# Sensor_Carousel.net
KiCad netlist of a schematic drawn in EAGLE
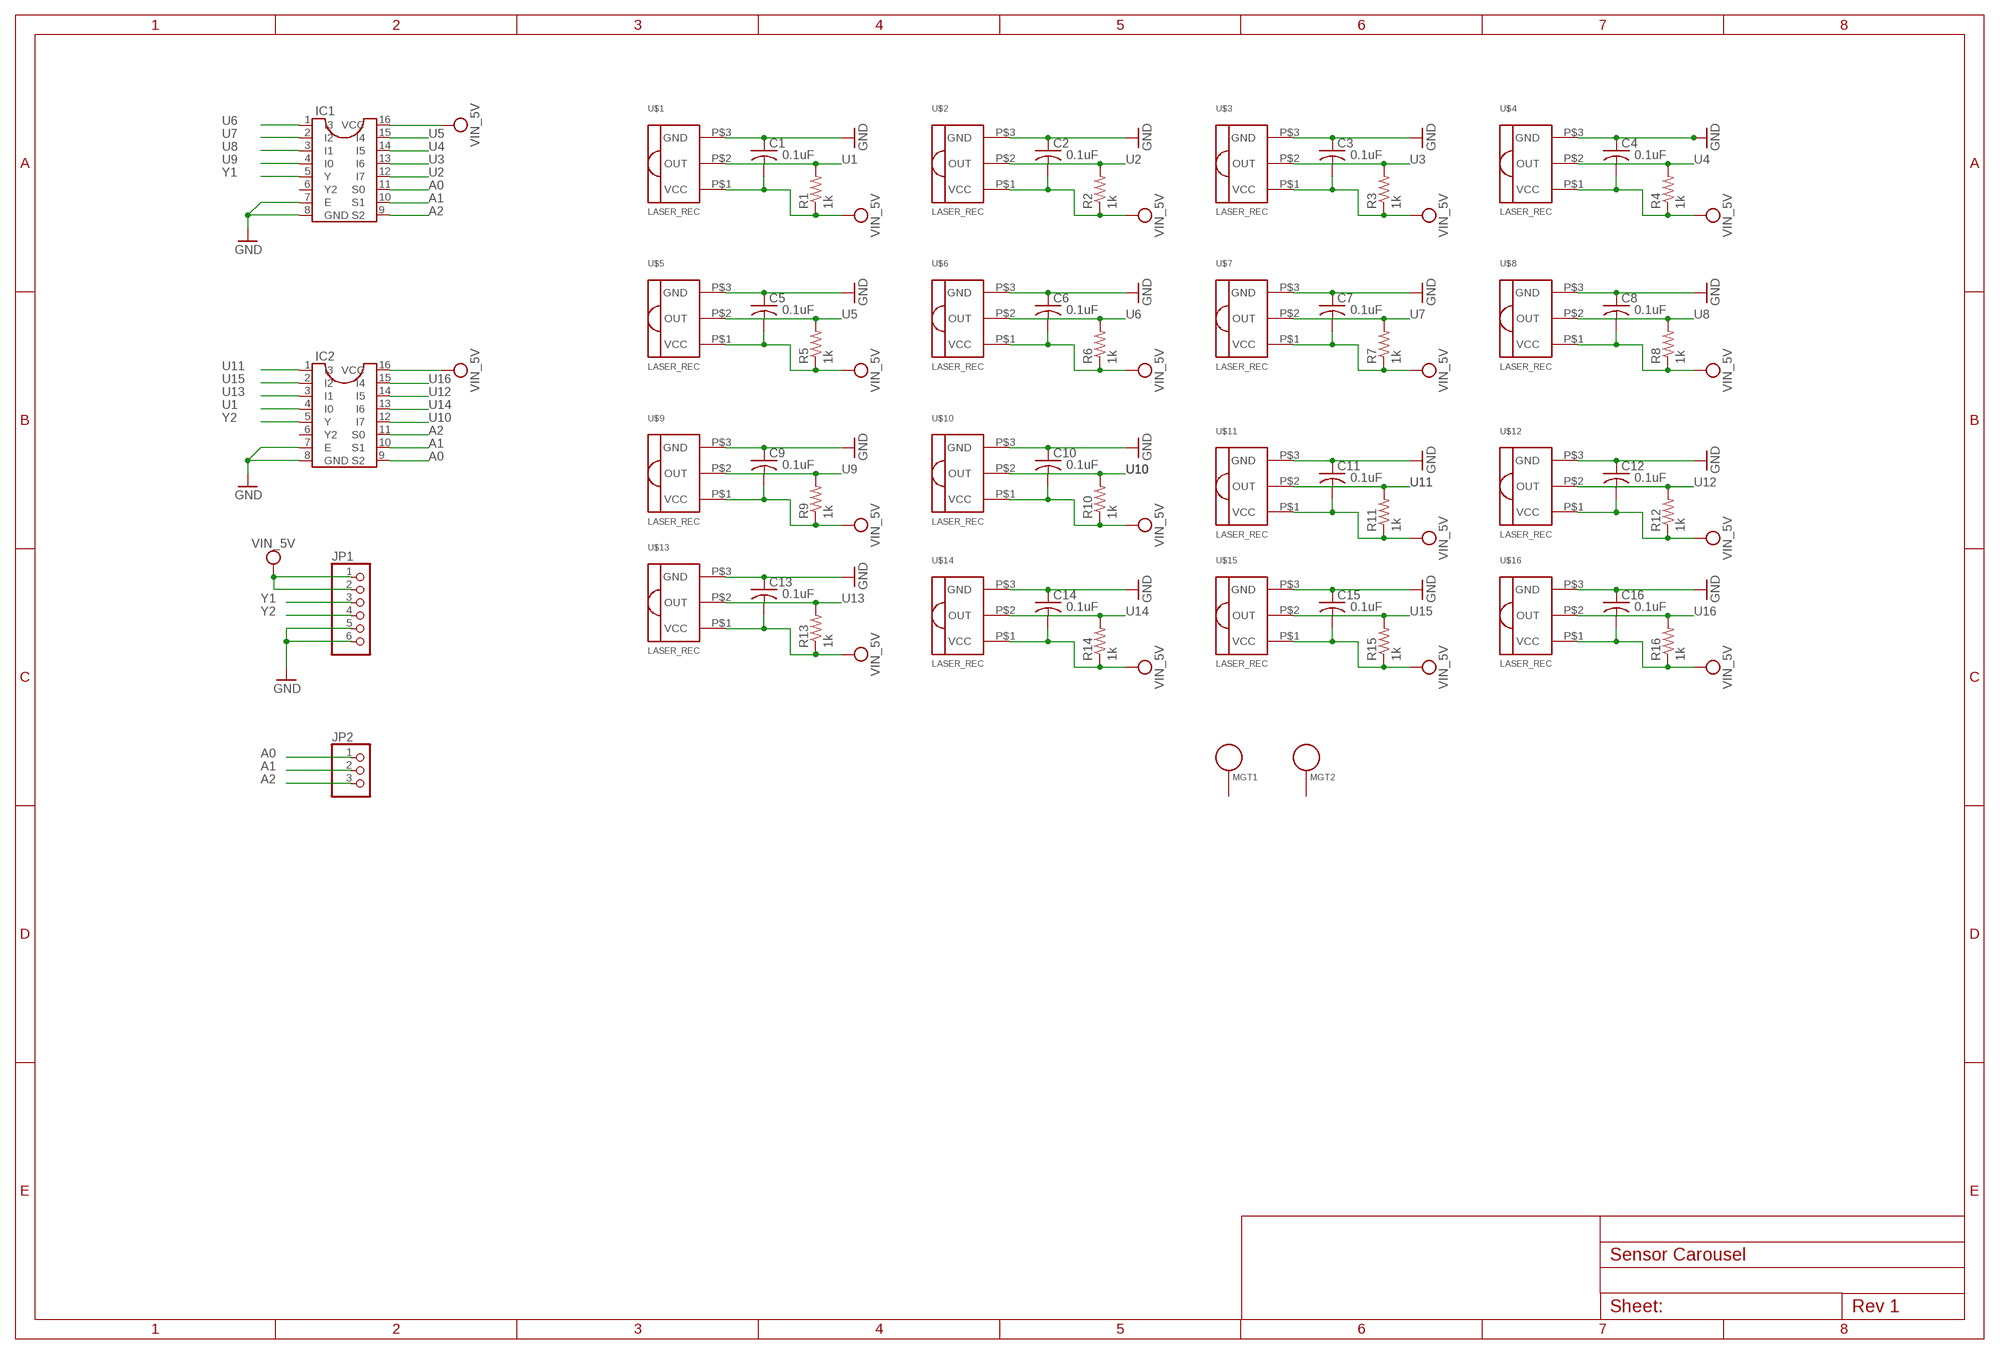
[diagram p0: schematic, sheet 1]

(export (version "E")
  (design (tool "Eeschema 10.0.6"))
  (components
    (comp (ref "C1")
      (value "0.1uF")
      (footprint "eagle-import:C025-024X044")
      (libsource (lib "eagle-import") (part "C-US025-024X044"))
    )
    (comp (ref "C2")
      (value "0.1uF")
      (footprint "eagle-import:C025-024X044")
      (libsource (lib "eagle-import") (part "C-US025-024X044"))
    )
    (comp (ref "C3")
      (value "0.1uF")
      (footprint "eagle-import:C025-024X044")
      (libsource (lib "eagle-import") (part "C-US025-024X044"))
    )
    (comp (ref "C4")
      (value "0.1uF")
      (footprint "eagle-import:C025-024X044")
      (libsource (lib "eagle-import") (part "C-US025-024X044"))
    )
    (comp (ref "C5")
      (value "0.1uF")
      (footprint "eagle-import:C025-024X044")
      (libsource (lib "eagle-import") (part "C-US025-024X044"))
    )
    (comp (ref "C6")
      (value "0.1uF")
      (footprint "eagle-import:C025-024X044")
      (libsource (lib "eagle-import") (part "C-US025-024X044"))
    )
    (comp (ref "C7")
      (value "0.1uF")
      (footprint "eagle-import:C025-024X044")
      (libsource (lib "eagle-import") (part "C-US025-024X044"))
    )
    (comp (ref "C8")
      (value "0.1uF")
      (footprint "eagle-import:C025-024X044")
      (libsource (lib "eagle-import") (part "C-US025-024X044"))
    )
    (comp (ref "C9")
      (value "0.1uF")
      (footprint "eagle-import:C025-024X044")
      (libsource (lib "eagle-import") (part "C-US025-024X044"))
    )
    (comp (ref "C10")
      (value "0.1uF")
      (footprint "eagle-import:C025-024X044")
      (libsource (lib "eagle-import") (part "C-US025-024X044"))
    )
    (comp (ref "C11")
      (value "0.1uF")
      (footprint "eagle-import:C025-024X044")
      (libsource (lib "eagle-import") (part "C-US025-024X044"))
    )
    (comp (ref "C12")
      (value "0.1uF")
      (footprint "eagle-import:C025-024X044")
      (libsource (lib "eagle-import") (part "C-US025-024X044"))
    )
    (comp (ref "C13")
      (value "0.1uF")
      (footprint "eagle-import:C025-024X044")
      (libsource (lib "eagle-import") (part "C-US025-024X044"))
    )
    (comp (ref "C14")
      (value "0.1uF")
      (footprint "eagle-import:C025-024X044")
      (libsource (lib "eagle-import") (part "C-US025-024X044"))
    )
    (comp (ref "C15")
      (value "0.1uF")
      (footprint "eagle-import:C025-024X044")
      (libsource (lib "eagle-import") (part "C-US025-024X044"))
    )
    (comp (ref "C16")
      (value "0.1uF")
      (footprint "eagle-import:C025-024X044")
      (libsource (lib "eagle-import") (part "C-US025-024X044"))
    )
    (comp (ref "IC1")
      (value "CD74HCT151S")
      (footprint "eagle-import:CD74HCT151")
      (libsource (lib "eagle-import") (part "CD74HCT151S"))
    )
    (comp (ref "IC2")
      (value "CD74HCT151S")
      (footprint "eagle-import:CD74HCT151")
      (libsource (lib "eagle-import") (part "CD74HCT151S"))
    )
    (comp (ref "JP1")
      (value "PINHD-1X6")
      (footprint "eagle-import:1X06")
      (libsource (lib "eagle-import") (part "PINHD-1X6"))
    )
    (comp (ref "JP2")
      (value "PINHD-1X3")
      (footprint "eagle-import:1X03")
      (libsource (lib "eagle-import") (part "PINHD-1X3"))
    )
    (comp (ref "MGT1")
      (value "MOUNTING_HOLE")
      (footprint "eagle-import:MOUNTING_HOLE")
      (libsource (lib "eagle-import") (part "MOUNTING_HOLE"))
    )
    (comp (ref "MGT2")
      (value "MOUNTING_HOLE")
      (footprint "eagle-import:MOUNTING_HOLE")
      (libsource (lib "eagle-import") (part "MOUNTING_HOLE"))
    )
    (comp (ref "R1")
      (value "1k")
      (footprint "eagle-import:0204V")
      (libsource (lib "eagle-import") (part "R-US_0204/2V"))
    )
    (comp (ref "R2")
      (value "1k")
      (footprint "eagle-import:0204V")
      (libsource (lib "eagle-import") (part "R-US_0204/2V"))
    )
    (comp (ref "R3")
      (value "1k")
      (footprint "eagle-import:0204V")
      (libsource (lib "eagle-import") (part "R-US_0204/2V"))
    )
    (comp (ref "R4")
      (value "1k")
      (footprint "eagle-import:0204V")
      (libsource (lib "eagle-import") (part "R-US_0204/2V"))
    )
    (comp (ref "R5")
      (value "1k")
      (footprint "eagle-import:0204V")
      (libsource (lib "eagle-import") (part "R-US_0204/2V"))
    )
    (comp (ref "R6")
      (value "1k")
      (footprint "eagle-import:0204V")
      (libsource (lib "eagle-import") (part "R-US_0204/2V"))
    )
    (comp (ref "R7")
      (value "1k")
      (footprint "eagle-import:0204V")
      (libsource (lib "eagle-import") (part "R-US_0204/2V"))
    )
    (comp (ref "R8")
      (value "1k")
      (footprint "eagle-import:0204V")
      (libsource (lib "eagle-import") (part "R-US_0204/2V"))
    )
    (comp (ref "R9")
      (value "1k")
      (footprint "eagle-import:0204V")
      (libsource (lib "eagle-import") (part "R-US_0204/2V"))
    )
    (comp (ref "R10")
      (value "1k")
      (footprint "eagle-import:0204V")
      (libsource (lib "eagle-import") (part "R-US_0204/2V"))
    )
    (comp (ref "R11")
      (value "1k")
      (footprint "eagle-import:0204V")
      (libsource (lib "eagle-import") (part "R-US_0204/2V"))
    )
    (comp (ref "R12")
      (value "1k")
      (footprint "eagle-import:0204V")
      (libsource (lib "eagle-import") (part "R-US_0204/2V"))
    )
    (comp (ref "R13")
      (value "1k")
      (footprint "eagle-import:0204V")
      (libsource (lib "eagle-import") (part "R-US_0204/2V"))
    )
    (comp (ref "R14")
      (value "1k")
      (footprint "eagle-import:0204V")
      (libsource (lib "eagle-import") (part "R-US_0204/2V"))
    )
    (comp (ref "R15")
      (value "1k")
      (footprint "eagle-import:0204V")
      (libsource (lib "eagle-import") (part "R-US_0204/2V"))
    )
    (comp (ref "R16")
      (value "1k")
      (footprint "eagle-import:0204V")
      (libsource (lib "eagle-import") (part "R-US_0204/2V"))
    )
    (comp (ref "U$1")
      (value "LASER_REC")
      (footprint "eagle-import:LSR_RC")
      (libsource (lib "eagle-import") (part "LASER_REC"))
    )
    (comp (ref "U$2")
      (value "LASER_REC")
      (footprint "eagle-import:LSR_RC")
      (libsource (lib "eagle-import") (part "LASER_REC"))
    )
    (comp (ref "U$3")
      (value "LASER_REC")
      (footprint "eagle-import:LSR_RC")
      (libsource (lib "eagle-import") (part "LASER_REC"))
    )
    (comp (ref "U$4")
      (value "LASER_REC")
      (footprint "eagle-import:LSR_RC")
      (libsource (lib "eagle-import") (part "LASER_REC"))
    )
    (comp (ref "U$5")
      (value "LASER_REC")
      (footprint "eagle-import:LSR_RC")
      (libsource (lib "eagle-import") (part "LASER_REC"))
    )
    (comp (ref "U$6")
      (value "LASER_REC")
      (footprint "eagle-import:LSR_RC")
      (libsource (lib "eagle-import") (part "LASER_REC"))
    )
    (comp (ref "U$7")
      (value "LASER_REC")
      (footprint "eagle-import:LSR_RC")
      (libsource (lib "eagle-import") (part "LASER_REC"))
    )
    (comp (ref "U$8")
      (value "LASER_REC")
      (footprint "eagle-import:LSR_RC")
      (libsource (lib "eagle-import") (part "LASER_REC"))
    )
    (comp (ref "U$9")
      (value "LASER_REC")
      (footprint "eagle-import:LSR_RC")
      (libsource (lib "eagle-import") (part "LASER_REC"))
    )
    (comp (ref "U$10")
      (value "LASER_REC")
      (footprint "eagle-import:LSR_RC")
      (libsource (lib "eagle-import") (part "LASER_REC"))
    )
    (comp (ref "U$11")
      (value "LASER_REC")
      (footprint "eagle-import:LSR_RC")
      (libsource (lib "eagle-import") (part "LASER_REC"))
    )
    (comp (ref "U$12")
      (value "LASER_REC")
      (footprint "eagle-import:LSR_RC")
      (libsource (lib "eagle-import") (part "LASER_REC"))
    )
    (comp (ref "U$13")
      (value "LASER_REC")
      (footprint "eagle-import:LSR_RC")
      (libsource (lib "eagle-import") (part "LASER_REC"))
    )
    (comp (ref "U$14")
      (value "LASER_REC")
      (footprint "eagle-import:LSR_RC")
      (libsource (lib "eagle-import") (part "LASER_REC"))
    )
    (comp (ref "U$15")
      (value "LASER_REC")
      (footprint "eagle-import:LSR_RC")
      (libsource (lib "eagle-import") (part "LASER_REC"))
    )
    (comp (ref "U$16")
      (value "LASER_REC")
      (footprint "eagle-import:LSR_RC")
      (libsource (lib "eagle-import") (part "LASER_REC"))
    )
  )
  (nets
    (net (code "1") (name "/A0") (class "Default")
      (node (ref "IC1") (pin "11") (pinfunction "S0_11") (pintype "input"))
      (node (ref "IC2") (pin "9") (pinfunction "S2_9") (pintype "input"))
      (node (ref "JP2") (pin "1") (pinfunction "1_1") (pintype "passive"))
    )
    (net (code "2") (name "/A1") (class "Default")
      (node (ref "IC1") (pin "10") (pinfunction "S1_10") (pintype "input"))
      (node (ref "IC2") (pin "10") (pinfunction "S1_10") (pintype "input"))
      (node (ref "JP2") (pin "2") (pinfunction "2_2") (pintype "passive"))
    )
    (net (code "3") (name "/A2") (class "Default")
      (node (ref "IC1") (pin "9") (pinfunction "S2_9") (pintype "input"))
      (node (ref "IC2") (pin "11") (pinfunction "S0_11") (pintype "input"))
      (node (ref "JP2") (pin "3") (pinfunction "3_3") (pintype "passive"))
    )
    (net (code "4") (name "/U1") (class "Default")
      (node (ref "IC2") (pin "4") (pinfunction "I0_4") (pintype "input"))
      (node (ref "R1") (pin "2") (pinfunction "2_2") (pintype "passive"))
      (node (ref "U$1") (pin "P$2") (pinfunction "OUT_P$2") (pintype "output"))
    )
    (net (code "5") (name "/U2") (class "Default")
      (node (ref "IC1") (pin "12") (pinfunction "I7_12") (pintype "input"))
      (node (ref "R2") (pin "2") (pinfunction "2_2") (pintype "passive"))
      (node (ref "U$2") (pin "P$2") (pinfunction "OUT_P$2") (pintype "output"))
    )
    (net (code "6") (name "/U3") (class "Default")
      (node (ref "IC1") (pin "13") (pinfunction "I6_13") (pintype "input"))
      (node (ref "R3") (pin "2") (pinfunction "2_2") (pintype "passive"))
      (node (ref "U$3") (pin "P$2") (pinfunction "OUT_P$2") (pintype "output"))
    )
    (net (code "7") (name "/U4") (class "Default")
      (node (ref "IC1") (pin "14") (pinfunction "I5_14") (pintype "input"))
      (node (ref "R4") (pin "2") (pinfunction "2_2") (pintype "passive"))
      (node (ref "U$4") (pin "P$2") (pinfunction "OUT_P$2") (pintype "output"))
    )
    (net (code "8") (name "/U5") (class "Default")
      (node (ref "IC1") (pin "15") (pinfunction "I4_15") (pintype "input"))
      (node (ref "R5") (pin "2") (pinfunction "2_2") (pintype "passive"))
      (node (ref "U$5") (pin "P$2") (pinfunction "OUT_P$2") (pintype "output"))
    )
    (net (code "9") (name "/U6") (class "Default")
      (node (ref "IC1") (pin "1") (pinfunction "I3_1") (pintype "input"))
      (node (ref "R6") (pin "2") (pinfunction "2_2") (pintype "passive"))
      (node (ref "U$6") (pin "P$2") (pinfunction "OUT_P$2") (pintype "output"))
    )
    (net (code "10") (name "/U7") (class "Default")
      (node (ref "IC1") (pin "2") (pinfunction "I2_2") (pintype "input"))
      (node (ref "R7") (pin "2") (pinfunction "2_2") (pintype "passive"))
      (node (ref "U$7") (pin "P$2") (pinfunction "OUT_P$2") (pintype "output"))
    )
    (net (code "11") (name "/U8") (class "Default")
      (node (ref "IC1") (pin "3") (pinfunction "I1_3") (pintype "input"))
      (node (ref "R8") (pin "2") (pinfunction "2_2") (pintype "passive"))
      (node (ref "U$8") (pin "P$2") (pinfunction "OUT_P$2") (pintype "output"))
    )
    (net (code "12") (name "/U9") (class "Default")
      (node (ref "IC1") (pin "4") (pinfunction "I0_4") (pintype "input"))
      (node (ref "R9") (pin "2") (pinfunction "2_2") (pintype "passive"))
      (node (ref "U$9") (pin "P$2") (pinfunction "OUT_P$2") (pintype "output"))
    )
    (net (code "13") (name "/U10") (class "Default")
      (node (ref "IC2") (pin "12") (pinfunction "I7_12") (pintype "input"))
      (node (ref "R10") (pin "2") (pinfunction "2_2") (pintype "passive"))
      (node (ref "U$10") (pin "P$2") (pinfunction "OUT_P$2") (pintype "output"))
    )
    (net (code "14") (name "/U11") (class "Default")
      (node (ref "IC2") (pin "1") (pinfunction "I3_1") (pintype "input"))
      (node (ref "R11") (pin "2") (pinfunction "2_2") (pintype "passive"))
      (node (ref "U$11") (pin "P$2") (pinfunction "OUT_P$2") (pintype "output"))
    )
    (net (code "15") (name "/U12") (class "Default")
      (node (ref "IC2") (pin "14") (pinfunction "I5_14") (pintype "input"))
      (node (ref "R12") (pin "2") (pinfunction "2_2") (pintype "passive"))
      (node (ref "U$12") (pin "P$2") (pinfunction "OUT_P$2") (pintype "output"))
    )
    (net (code "16") (name "/U13") (class "Default")
      (node (ref "IC2") (pin "3") (pinfunction "I1_3") (pintype "input"))
      (node (ref "R13") (pin "2") (pinfunction "2_2") (pintype "passive"))
      (node (ref "U$13") (pin "P$2") (pinfunction "OUT_P$2") (pintype "output"))
    )
    (net (code "17") (name "/U14") (class "Default")
      (node (ref "IC2") (pin "13") (pinfunction "I6_13") (pintype "input"))
      (node (ref "R14") (pin "2") (pinfunction "2_2") (pintype "passive"))
      (node (ref "U$14") (pin "P$2") (pinfunction "OUT_P$2") (pintype "output"))
    )
    (net (code "18") (name "/U15") (class "Default")
      (node (ref "IC2") (pin "2") (pinfunction "I2_2") (pintype "input"))
      (node (ref "R15") (pin "2") (pinfunction "2_2") (pintype "passive"))
      (node (ref "U$15") (pin "P$2") (pinfunction "OUT_P$2") (pintype "output"))
    )
    (net (code "19") (name "/U16") (class "Default")
      (node (ref "IC2") (pin "15") (pinfunction "I4_15") (pintype "input"))
      (node (ref "R16") (pin "2") (pinfunction "2_2") (pintype "passive"))
      (node (ref "U$16") (pin "P$2") (pinfunction "OUT_P$2") (pintype "output"))
    )
    (net (code "20") (name "/Y1") (class "Default")
      (node (ref "IC1") (pin "5") (pinfunction "Y_5") (pintype "output"))
      (node (ref "JP1") (pin "3") (pinfunction "3_3") (pintype "passive"))
    )
    (net (code "21") (name "/Y2") (class "Default")
      (node (ref "IC2") (pin "5") (pinfunction "Y_5") (pintype "output"))
      (node (ref "JP1") (pin "4") (pinfunction "4_4") (pintype "passive"))
    )
    (net (code "22") (name "GND") (class "Default")
      (node (ref "C1") (pin "1") (pinfunction "1_1") (pintype "passive"))
      (node (ref "C10") (pin "1") (pinfunction "1_1") (pintype "passive"))
      (node (ref "C11") (pin "1") (pinfunction "1_1") (pintype "passive"))
      (node (ref "C12") (pin "1") (pinfunction "1_1") (pintype "passive"))
      (node (ref "C13") (pin "1") (pinfunction "1_1") (pintype "passive"))
      (node (ref "C14") (pin "1") (pinfunction "1_1") (pintype "passive"))
      (node (ref "C15") (pin "1") (pinfunction "1_1") (pintype "passive"))
      (node (ref "C16") (pin "1") (pinfunction "1_1") (pintype "passive"))
      (node (ref "C2") (pin "1") (pinfunction "1_1") (pintype "passive"))
      (node (ref "C3") (pin "1") (pinfunction "1_1") (pintype "passive"))
      (node (ref "C4") (pin "1") (pinfunction "1_1") (pintype "passive"))
      (node (ref "C5") (pin "1") (pinfunction "1_1") (pintype "passive"))
      (node (ref "C6") (pin "1") (pinfunction "1_1") (pintype "passive"))
      (node (ref "C7") (pin "1") (pinfunction "1_1") (pintype "passive"))
      (node (ref "C8") (pin "1") (pinfunction "1_1") (pintype "passive"))
      (node (ref "C9") (pin "1") (pinfunction "1_1") (pintype "passive"))
      (node (ref "IC1") (pin "7") (pinfunction "E_7") (pintype "power_in"))
      (node (ref "IC1") (pin "8") (pinfunction "GND_8") (pintype "power_in"))
      (node (ref "IC2") (pin "7") (pinfunction "E_7") (pintype "power_in"))
      (node (ref "IC2") (pin "8") (pinfunction "GND_8") (pintype "power_in"))
      (node (ref "JP1") (pin "5") (pinfunction "5_5") (pintype "passive"))
      (node (ref "JP1") (pin "6") (pinfunction "6_6") (pintype "passive"))
      (node (ref "U$1") (pin "P$3") (pinfunction "GND_P$3") (pintype "power_in"))
      (node (ref "U$10") (pin "P$3") (pinfunction "GND_P$3") (pintype "power_in"))
      (node (ref "U$11") (pin "P$3") (pinfunction "GND_P$3") (pintype "power_in"))
      (node (ref "U$12") (pin "P$3") (pinfunction "GND_P$3") (pintype "power_in"))
      (node (ref "U$13") (pin "P$3") (pinfunction "GND_P$3") (pintype "power_in"))
      (node (ref "U$14") (pin "P$3") (pinfunction "GND_P$3") (pintype "power_in"))
      (node (ref "U$15") (pin "P$3") (pinfunction "GND_P$3") (pintype "power_in"))
      (node (ref "U$16") (pin "P$3") (pinfunction "GND_P$3") (pintype "power_in"))
      (node (ref "U$2") (pin "P$3") (pinfunction "GND_P$3") (pintype "power_in"))
      (node (ref "U$3") (pin "P$3") (pinfunction "GND_P$3") (pintype "power_in"))
      (node (ref "U$4") (pin "P$3") (pinfunction "GND_P$3") (pintype "power_in"))
      (node (ref "U$5") (pin "P$3") (pinfunction "GND_P$3") (pintype "power_in"))
      (node (ref "U$6") (pin "P$3") (pinfunction "GND_P$3") (pintype "power_in"))
      (node (ref "U$7") (pin "P$3") (pinfunction "GND_P$3") (pintype "power_in"))
      (node (ref "U$8") (pin "P$3") (pinfunction "GND_P$3") (pintype "power_in"))
      (node (ref "U$9") (pin "P$3") (pinfunction "GND_P$3") (pintype "power_in"))
    )
    (net (code "23") (name "VIN_5V") (class "Default")
      (node (ref "C1") (pin "2") (pinfunction "2_2") (pintype "passive"))
      (node (ref "C10") (pin "2") (pinfunction "2_2") (pintype "passive"))
      (node (ref "C11") (pin "2") (pinfunction "2_2") (pintype "passive"))
      (node (ref "C12") (pin "2") (pinfunction "2_2") (pintype "passive"))
      (node (ref "C13") (pin "2") (pinfunction "2_2") (pintype "passive"))
      (node (ref "C14") (pin "2") (pinfunction "2_2") (pintype "passive"))
      (node (ref "C15") (pin "2") (pinfunction "2_2") (pintype "passive"))
      (node (ref "C16") (pin "2") (pinfunction "2_2") (pintype "passive"))
      (node (ref "C2") (pin "2") (pinfunction "2_2") (pintype "passive"))
      (node (ref "C3") (pin "2") (pinfunction "2_2") (pintype "passive"))
      (node (ref "C4") (pin "2") (pinfunction "2_2") (pintype "passive"))
      (node (ref "C5") (pin "2") (pinfunction "2_2") (pintype "passive"))
      (node (ref "C6") (pin "2") (pinfunction "2_2") (pintype "passive"))
      (node (ref "C7") (pin "2") (pinfunction "2_2") (pintype "passive"))
      (node (ref "C8") (pin "2") (pinfunction "2_2") (pintype "passive"))
      (node (ref "C9") (pin "2") (pinfunction "2_2") (pintype "passive"))
      (node (ref "IC1") (pin "16") (pinfunction "VCC_16") (pintype "power_in"))
      (node (ref "IC2") (pin "16") (pinfunction "VCC_16") (pintype "power_in"))
      (node (ref "JP1") (pin "1") (pinfunction "1_1") (pintype "passive"))
      (node (ref "JP1") (pin "2") (pinfunction "2_2") (pintype "passive"))
      (node (ref "R1") (pin "1") (pinfunction "1_1") (pintype "passive"))
      (node (ref "R10") (pin "1") (pinfunction "1_1") (pintype "passive"))
      (node (ref "R11") (pin "1") (pinfunction "1_1") (pintype "passive"))
      (node (ref "R12") (pin "1") (pinfunction "1_1") (pintype "passive"))
      (node (ref "R13") (pin "1") (pinfunction "1_1") (pintype "passive"))
      (node (ref "R14") (pin "1") (pinfunction "1_1") (pintype "passive"))
      (node (ref "R15") (pin "1") (pinfunction "1_1") (pintype "passive"))
      (node (ref "R16") (pin "1") (pinfunction "1_1") (pintype "passive"))
      (node (ref "R2") (pin "1") (pinfunction "1_1") (pintype "passive"))
      (node (ref "R3") (pin "1") (pinfunction "1_1") (pintype "passive"))
      (node (ref "R4") (pin "1") (pinfunction "1_1") (pintype "passive"))
      (node (ref "R5") (pin "1") (pinfunction "1_1") (pintype "passive"))
      (node (ref "R6") (pin "1") (pinfunction "1_1") (pintype "passive"))
      (node (ref "R7") (pin "1") (pinfunction "1_1") (pintype "passive"))
      (node (ref "R8") (pin "1") (pinfunction "1_1") (pintype "passive"))
      (node (ref "R9") (pin "1") (pinfunction "1_1") (pintype "passive"))
      (node (ref "U$1") (pin "P$1") (pinfunction "VCC_P$1") (pintype "power_in"))
      (node (ref "U$10") (pin "P$1") (pinfunction "VCC_P$1") (pintype "power_in"))
      (node (ref "U$11") (pin "P$1") (pinfunction "VCC_P$1") (pintype "power_in"))
      (node (ref "U$12") (pin "P$1") (pinfunction "VCC_P$1") (pintype "power_in"))
      (node (ref "U$13") (pin "P$1") (pinfunction "VCC_P$1") (pintype "power_in"))
      (node (ref "U$14") (pin "P$1") (pinfunction "VCC_P$1") (pintype "power_in"))
      (node (ref "U$15") (pin "P$1") (pinfunction "VCC_P$1") (pintype "power_in"))
      (node (ref "U$16") (pin "P$1") (pinfunction "VCC_P$1") (pintype "power_in"))
      (node (ref "U$2") (pin "P$1") (pinfunction "VCC_P$1") (pintype "power_in"))
      (node (ref "U$3") (pin "P$1") (pinfunction "VCC_P$1") (pintype "power_in"))
      (node (ref "U$4") (pin "P$1") (pinfunction "VCC_P$1") (pintype "power_in"))
      (node (ref "U$5") (pin "P$1") (pinfunction "VCC_P$1") (pintype "power_in"))
      (node (ref "U$6") (pin "P$1") (pinfunction "VCC_P$1") (pintype "power_in"))
      (node (ref "U$7") (pin "P$1") (pinfunction "VCC_P$1") (pintype "power_in"))
      (node (ref "U$8") (pin "P$1") (pinfunction "VCC_P$1") (pintype "power_in"))
      (node (ref "U$9") (pin "P$1") (pinfunction "VCC_P$1") (pintype "power_in"))
    )
    (net (code "24") (name "unconnected-(IC1-Y2-Pad6)") (class "Default")
      (node (ref "IC1") (pin "6") (pinfunction "Y2_6") (pintype "output"))
    )
    (net (code "25") (name "unconnected-(IC2-Y2-Pad6)") (class "Default")
      (node (ref "IC2") (pin "6") (pinfunction "Y2_6") (pintype "output"))
    )
    (net (code "26") (name "unconnected-(MGT1-PadP$1)") (class "Default")
      (node (ref "MGT1") (pin "P$1") (pinfunction "P$1_P$1") (pintype "bidirectional"))
    )
    (net (code "27") (name "unconnected-(MGT2-PadP$1)") (class "Default")
      (node (ref "MGT2") (pin "P$1") (pinfunction "P$1_P$1") (pintype "bidirectional"))
    )
  )
)
